# JTAG.net
KiCad netlist of a schematic drawn in Altium Designer
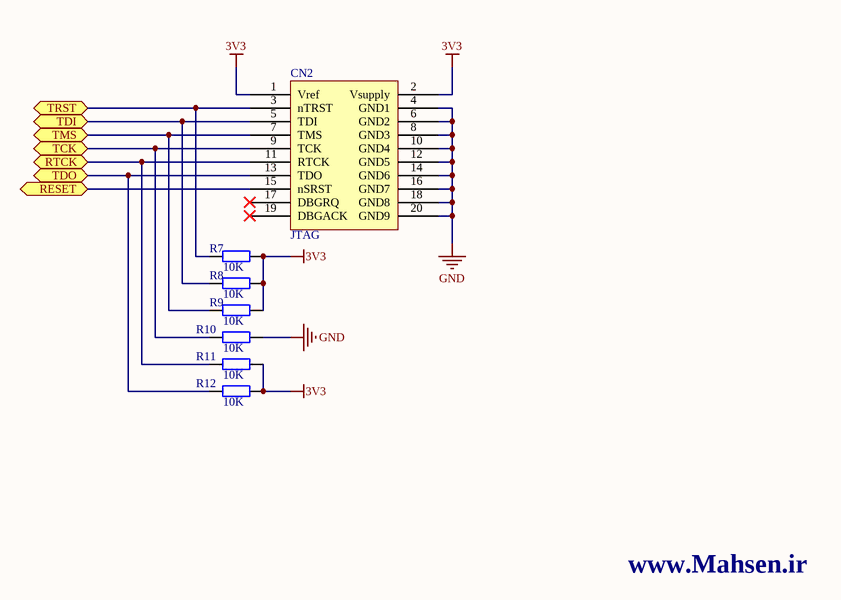
[diagram p0: JTAG.SchDoc]

(export (version "E")
  (design (tool "Eeschema 10.0.6"))
  (components
    (comp (ref "CN2") (value "JTAG") (footprint "FKV20SN") (libsource (lib "Lotfi") (part "JTAG")))
    (comp (ref "R7")
      (value "10K")
      (footprint "0805")
      (description "Resistor")
      (fields (field (name "PUBLISHER") "Altium Limited"))
      (libsource (lib "Miscellaneous Devices") (part "Res2"))
    )
    (comp (ref "R8")
      (value "10K")
      (footprint "0805")
      (description "Resistor")
      (fields (field (name "PUBLISHER") "Altium Limited"))
      (libsource (lib "Miscellaneous Devices") (part "Res2"))
    )
    (comp (ref "R9")
      (value "10K")
      (footprint "0805")
      (description "Resistor")
      (fields (field (name "PUBLISHER") "Altium Limited"))
      (libsource (lib "Miscellaneous Devices") (part "Res2"))
    )
    (comp (ref "R10")
      (value "10K")
      (footprint "0805")
      (description "Resistor")
      (fields (field (name "PUBLISHER") "Altium Limited"))
      (libsource (lib "Miscellaneous Devices") (part "Res2"))
    )
    (comp (ref "R11")
      (value "10K")
      (footprint "0805")
      (description "Resistor")
      (fields (field (name "PUBLISHER") "Altium Limited"))
      (libsource (lib "Miscellaneous Devices") (part "Res2"))
    )
    (comp (ref "R12")
      (value "10K")
      (footprint "0805")
      (description "Resistor")
      (fields (field (name "PUBLISHER") "Altium Limited"))
      (libsource (lib "Miscellaneous Devices") (part "Res2"))
    )
  )
  (nets
    (net (code "1") (name "/RESET") (class "Default")
      (node (ref "CN2") (pin "15") (pinfunction "nSRST_15") (pintype "passive"))
    )
    (net (code "2") (name "/RTCK") (class "Default")
      (node (ref "CN2") (pin "11") (pinfunction "RTCK_11") (pintype "passive"))
      (node (ref "R11") (pin "2") (pinfunction "2_2") (pintype "passive"))
    )
    (net (code "3") (name "/TCK") (class "Default")
      (node (ref "CN2") (pin "9") (pinfunction "TCK_9") (pintype "passive"))
      (node (ref "R10") (pin "2") (pinfunction "2_2") (pintype "passive"))
    )
    (net (code "4") (name "/TDI") (class "Default")
      (node (ref "CN2") (pin "5") (pinfunction "TDI_5") (pintype "passive"))
      (node (ref "R8") (pin "2") (pinfunction "2_2") (pintype "passive"))
    )
    (net (code "5") (name "/TDO") (class "Default")
      (node (ref "CN2") (pin "13") (pinfunction "TDO_13") (pintype "passive"))
      (node (ref "R12") (pin "2") (pinfunction "2_2") (pintype "passive"))
    )
    (net (code "6") (name "/TMS") (class "Default")
      (node (ref "CN2") (pin "7") (pinfunction "TMS_7") (pintype "passive"))
      (node (ref "R9") (pin "2") (pinfunction "2_2") (pintype "passive"))
    )
    (net (code "7") (name "/TRST") (class "Default")
      (node (ref "CN2") (pin "3") (pinfunction "nTRST_3") (pintype "passive"))
      (node (ref "R7") (pin "2") (pinfunction "2_2") (pintype "passive"))
    )
    (net (code "8") (name "3V3") (class "Default")
      (node (ref "CN2") (pin "1") (pinfunction "Vref_1") (pintype "passive"))
      (node (ref "CN2") (pin "2") (pinfunction "Vsupply_2") (pintype "passive"))
      (node (ref "R11") (pin "1") (pinfunction "1_1") (pintype "passive"))
      (node (ref "R12") (pin "1") (pinfunction "1_1") (pintype "passive"))
      (node (ref "R7") (pin "1") (pinfunction "1_1") (pintype "passive"))
      (node (ref "R8") (pin "1") (pinfunction "1_1") (pintype "passive"))
      (node (ref "R9") (pin "1") (pinfunction "1_1") (pintype "passive"))
    )
    (net (code "9") (name "GND") (class "Default")
      (node (ref "CN2") (pin "10") (pinfunction "GND4_10") (pintype "passive"))
      (node (ref "CN2") (pin "12") (pinfunction "GND5_12") (pintype "passive"))
      (node (ref "CN2") (pin "14") (pinfunction "GND6_14") (pintype "passive"))
      (node (ref "CN2") (pin "16") (pinfunction "GND7_16") (pintype "passive"))
      (node (ref "CN2") (pin "18") (pinfunction "GND8_18") (pintype "passive"))
      (node (ref "CN2") (pin "20") (pinfunction "GND9_20") (pintype "passive"))
      (node (ref "CN2") (pin "4") (pinfunction "GND1_4") (pintype "passive"))
      (node (ref "CN2") (pin "6") (pinfunction "GND2_6") (pintype "passive"))
      (node (ref "CN2") (pin "8") (pinfunction "GND3_8") (pintype "passive"))
      (node (ref "R10") (pin "1") (pinfunction "1_1") (pintype "passive"))
    )
    (net (code "10") (name "unconnected-(CN2-DBGACK-Pad19)") (class "Default")
      (node (ref "CN2") (pin "19") (pinfunction "DBGACK_19") (pintype "passive+no_connect"))
    )
    (net (code "11") (name "unconnected-(CN2-DBGRQ-Pad17)") (class "Default")
      (node (ref "CN2") (pin "17") (pinfunction "DBGRQ_17") (pintype "passive+no_connect"))
    )
  )
)
